# SmartVision.net
KiCad netlist of a schematic drawn in EAGLE
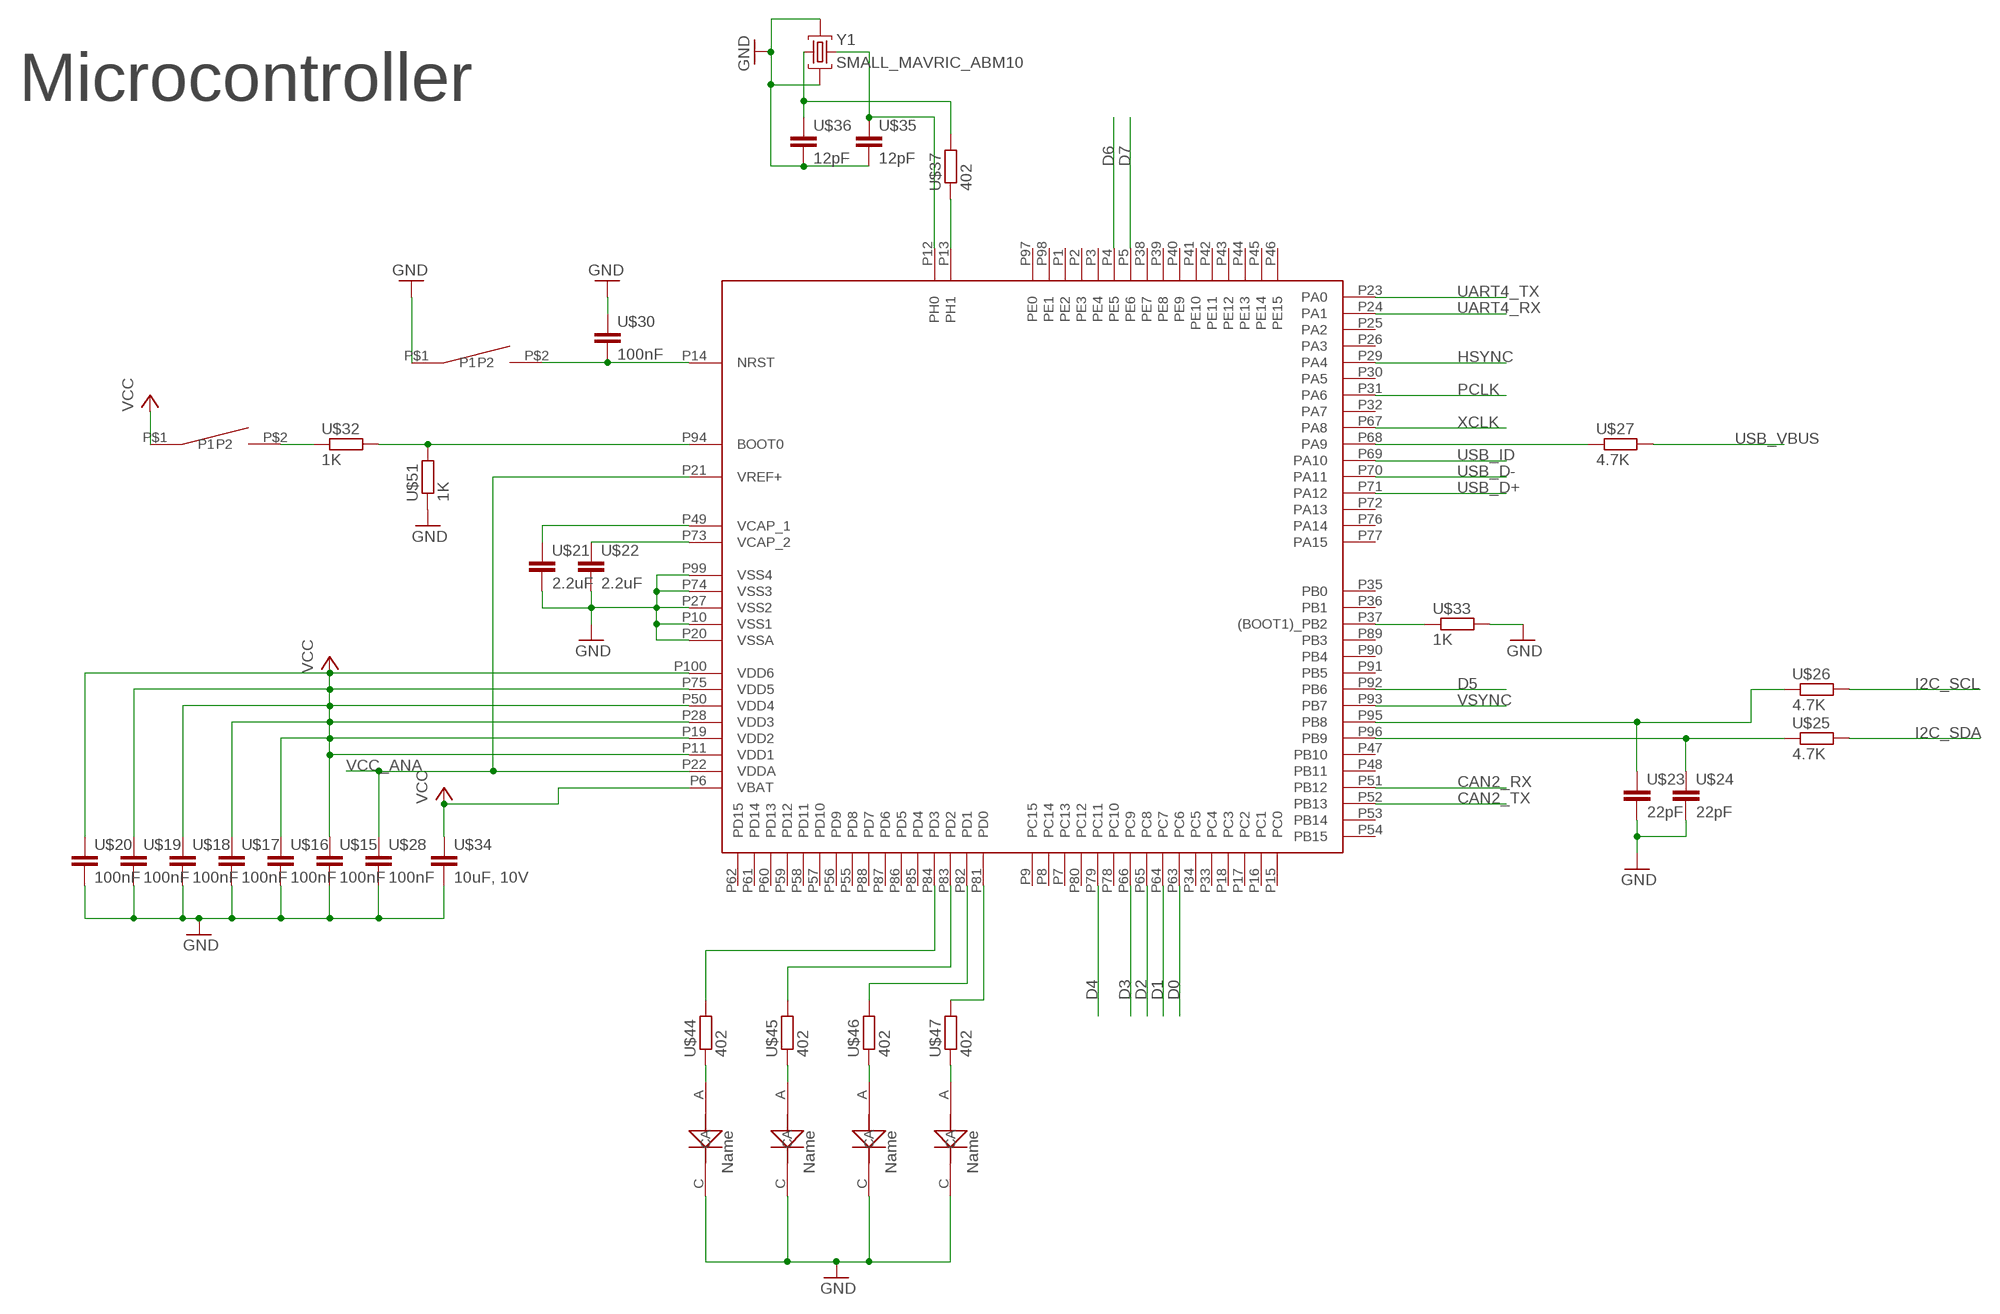
[diagram p0: schematic, sheet 1]
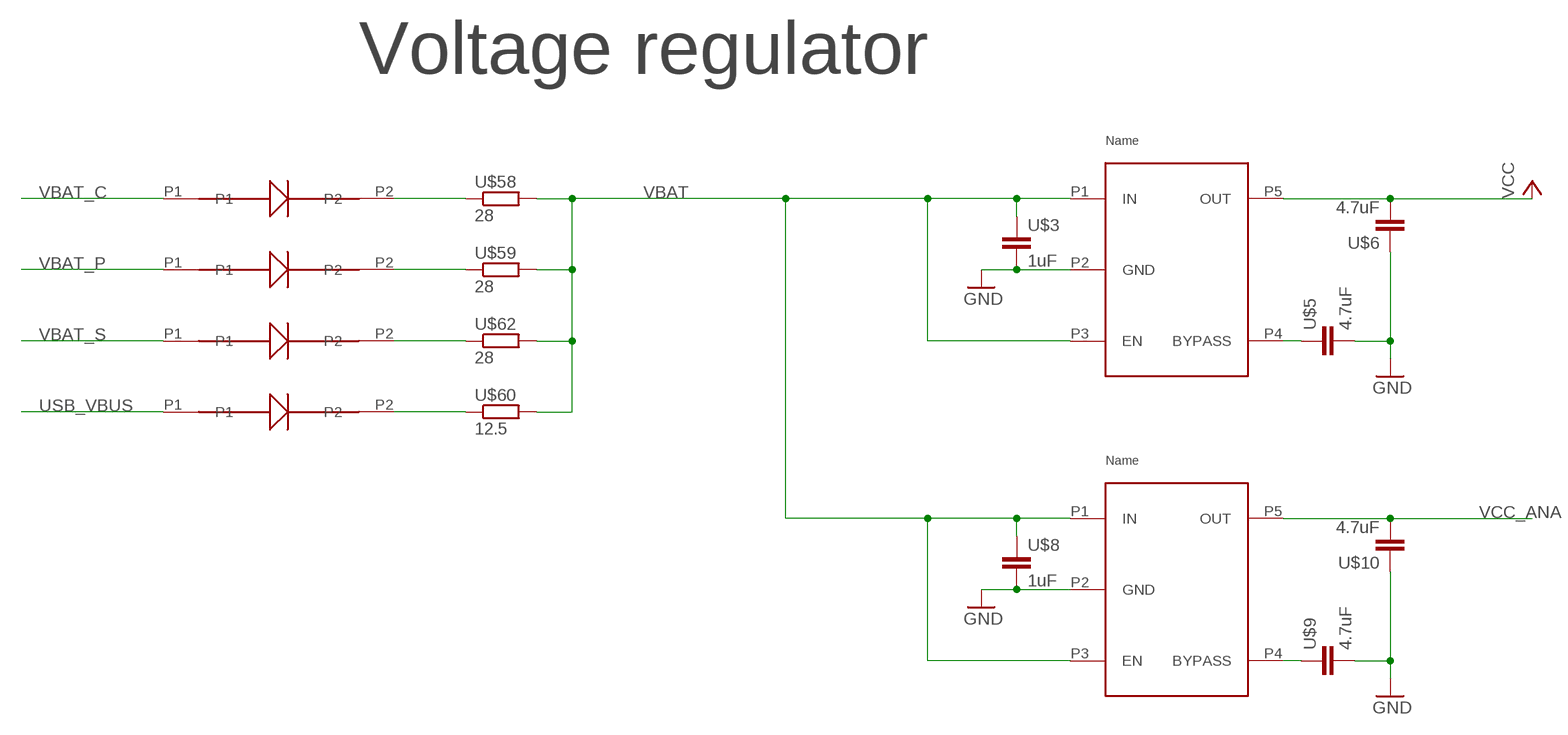
[diagram p1: schematic, sheet 2]
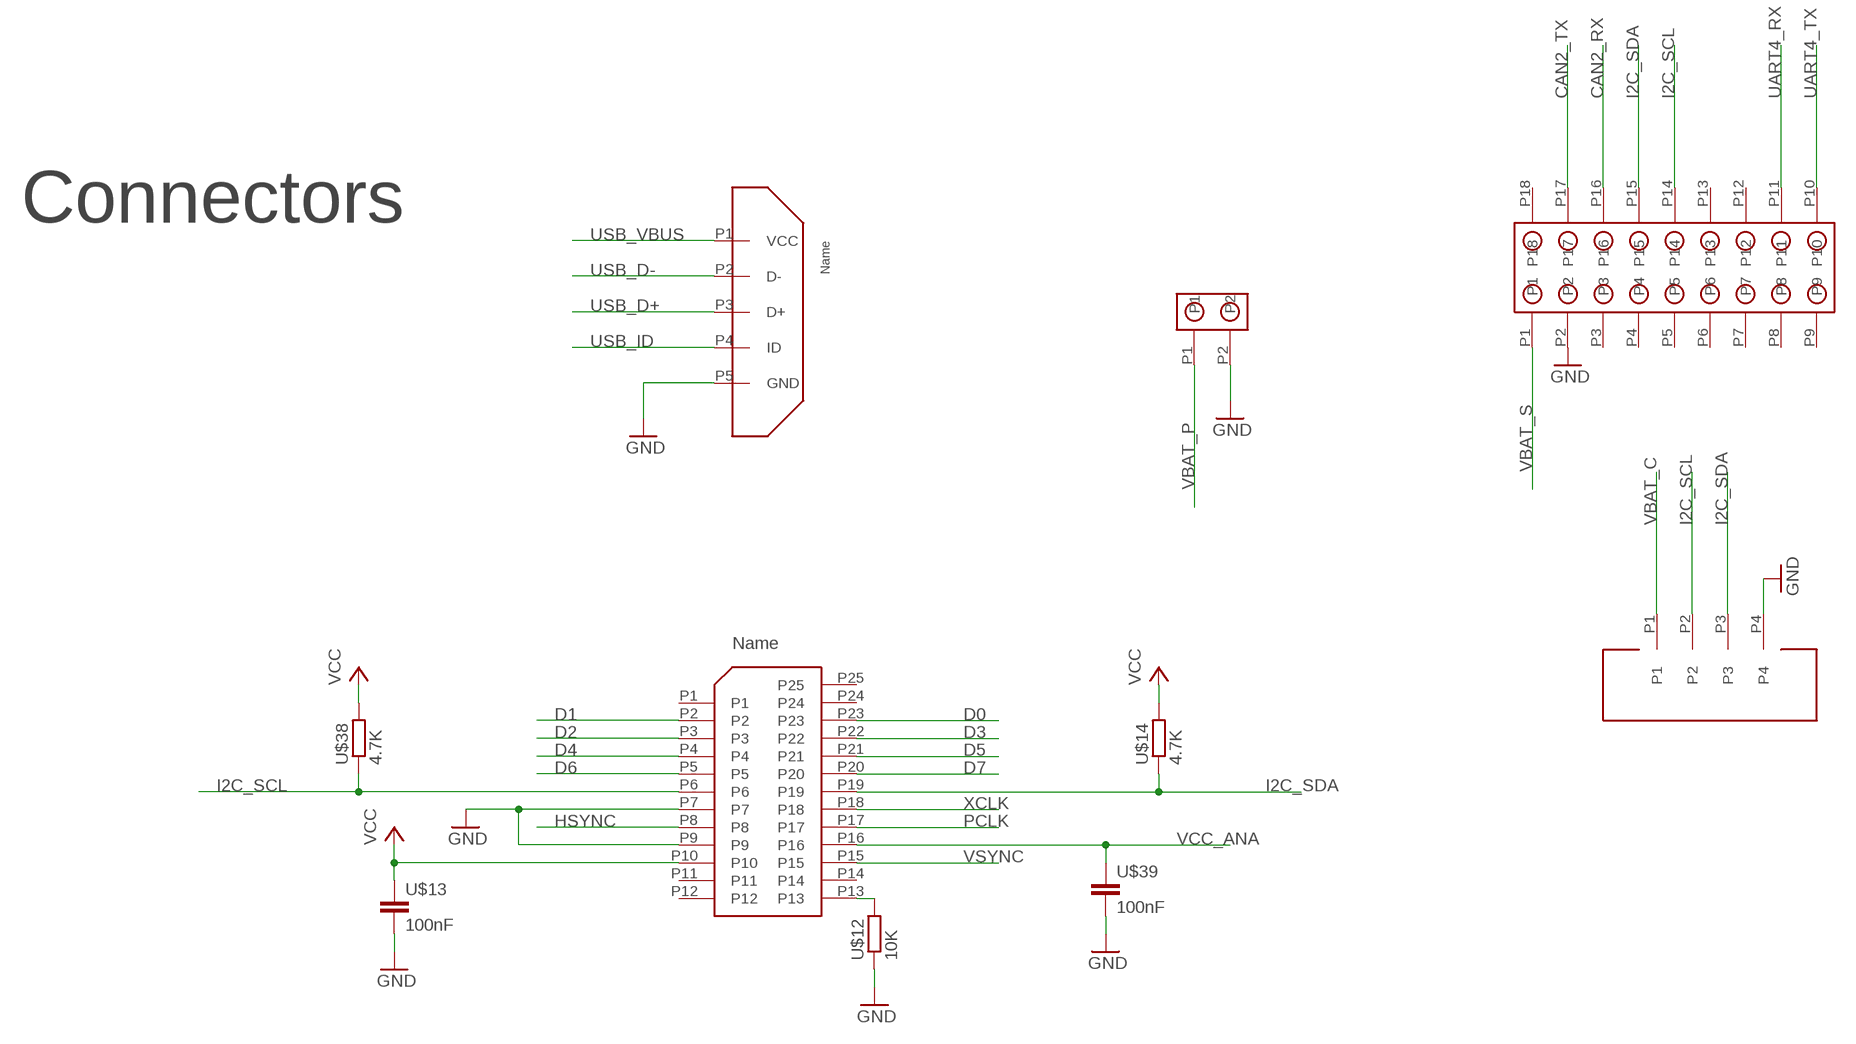
[diagram p2: schematic, sheet 3]
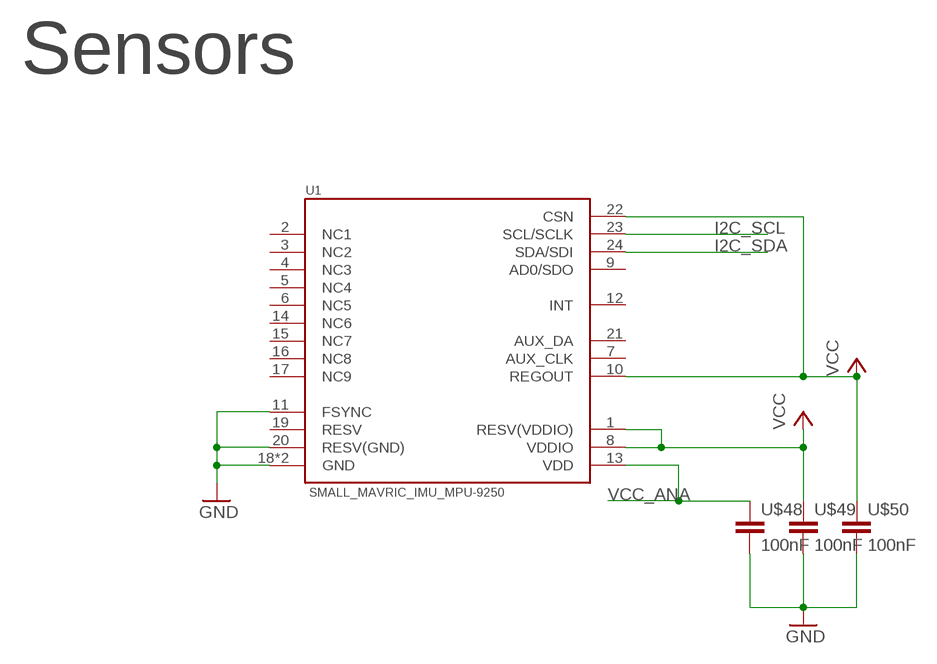
[diagram p3: schematic, sheet 4]

(export (version "E")
  (design (tool "Eeschema 10.0.6"))
  (components
    (comp (ref "U$1")
      (value "STM32F407VGT6-100")
      (footprint "eagle-import:STM32F407VGT6-100")
      (libsource (lib "eagle-import") (part "STM32F407VGT6-100"))
    )
    (comp (ref "U$15")
      (value "100nF")
      (footprint "eagle-import:SMALL_MAVRIC_SMALL_MAVRIC_CAPACITOR_C0402")
      (fields (field (name "PLACE_PART") "YES"))
      (libsource (lib "eagle-import") (part "SMALL_MAVRIC_CAPACITOR_C0402"))
    )
    (comp (ref "U$16")
      (value "100nF")
      (footprint "eagle-import:SMALL_MAVRIC_SMALL_MAVRIC_CAPACITOR_C0402")
      (fields (field (name "PLACE_PART") "YES"))
      (libsource (lib "eagle-import") (part "SMALL_MAVRIC_CAPACITOR_C0402"))
    )
    (comp (ref "U$17")
      (value "100nF")
      (footprint "eagle-import:SMALL_MAVRIC_SMALL_MAVRIC_CAPACITOR_C0402")
      (fields (field (name "PLACE_PART") "YES"))
      (libsource (lib "eagle-import") (part "SMALL_MAVRIC_CAPACITOR_C0402"))
    )
    (comp (ref "U$18")
      (value "100nF")
      (footprint "eagle-import:SMALL_MAVRIC_SMALL_MAVRIC_CAPACITOR_C0402")
      (fields (field (name "PLACE_PART") "YES"))
      (libsource (lib "eagle-import") (part "SMALL_MAVRIC_CAPACITOR_C0402"))
    )
    (comp (ref "U$19")
      (value "100nF")
      (footprint "eagle-import:SMALL_MAVRIC_SMALL_MAVRIC_CAPACITOR_C0402")
      (fields (field (name "PLACE_PART") "YES"))
      (libsource (lib "eagle-import") (part "SMALL_MAVRIC_CAPACITOR_C0402"))
    )
    (comp (ref "U$20")
      (value "100nF")
      (footprint "eagle-import:SMALL_MAVRIC_SMALL_MAVRIC_CAPACITOR_C0402")
      (fields (field (name "PLACE_PART") "YES"))
      (libsource (lib "eagle-import") (part "SMALL_MAVRIC_CAPACITOR_C0402"))
    )
    (comp (ref "U$21")
      (value "2.2uF")
      (footprint "eagle-import:SMALL_MAVRIC_SMALL_MAVRIC_CAPACITOR_C0402")
      (fields (field (name "PLACE_PART") "YES"))
      (libsource (lib "eagle-import") (part "SMALL_MAVRIC_CAPACITOR_C0402"))
    )
    (comp (ref "U$22")
      (value "2.2uF")
      (footprint "eagle-import:SMALL_MAVRIC_SMALL_MAVRIC_CAPACITOR_C0402")
      (fields (field (name "PLACE_PART") "YES"))
      (libsource (lib "eagle-import") (part "SMALL_MAVRIC_CAPACITOR_C0402"))
    )
    (comp (ref "U$23")
      (value "22pF")
      (footprint "eagle-import:SMALL_MAVRIC_SMALL_MAVRIC_CAPACITOR_C0402")
      (fields (field (name "PLACE_PART") "YES"))
      (libsource (lib "eagle-import") (part "SMALL_MAVRIC_CAPACITOR_C0402"))
    )
    (comp (ref "U$24")
      (value "22pF")
      (footprint "eagle-import:SMALL_MAVRIC_SMALL_MAVRIC_CAPACITOR_C0402")
      (fields (field (name "PLACE_PART") "YES"))
      (libsource (lib "eagle-import") (part "SMALL_MAVRIC_CAPACITOR_C0402"))
    )
    (comp (ref "U$25")
      (value "4.7K")
      (footprint "eagle-import:SMALL_MAVRIC_SMALL_MAVRIC_RESISTOR_R0402")
      (fields (field (name "PLACE_PART") "YES"))
      (libsource (lib "eagle-import") (part "SMALL_MAVRIC_RESISTOR_R0402"))
    )
    (comp (ref "U$26")
      (value "4.7K")
      (footprint "eagle-import:SMALL_MAVRIC_SMALL_MAVRIC_RESISTOR_R0402")
      (fields (field (name "PLACE_PART") "YES"))
      (libsource (lib "eagle-import") (part "SMALL_MAVRIC_RESISTOR_R0402"))
    )
    (comp (ref "U$27")
      (value "4.7K")
      (footprint "eagle-import:SMALL_MAVRIC_SMALL_MAVRIC_RESISTOR_R0402")
      (fields (field (name "PLACE_PART") "YES"))
      (libsource (lib "eagle-import") (part "SMALL_MAVRIC_RESISTOR_R0402"))
    )
    (comp (ref "U$28")
      (value "100nF")
      (footprint "eagle-import:SMALL_MAVRIC_SMALL_MAVRIC_CAPACITOR_C0402")
      (fields (field (name "PLACE_PART") "YES"))
      (libsource (lib "eagle-import") (part "SMALL_MAVRIC_CAPACITOR_C0402"))
    )
    (comp (ref "U$29")
      (value "SWITCH_OFF_(ON)")
      (footprint "eagle-import:SWITCH_OFF_(ON)")
      (libsource (lib "eagle-import") (part "SWITCH_OFF_(ON)"))
    )
    (comp (ref "U$30")
      (value "100nF")
      (footprint "eagle-import:SMALL_MAVRIC_SMALL_MAVRIC_CAPACITOR_C0402")
      (fields (field (name "PLACE_PART") "YES"))
      (libsource (lib "eagle-import") (part "SMALL_MAVRIC_CAPACITOR_C0402"))
    )
    (comp (ref "U$31")
      (value "SWITCH_OFF_(ON)")
      (footprint "eagle-import:SWITCH_OFF_(ON)")
      (libsource (lib "eagle-import") (part "SWITCH_OFF_(ON)"))
    )
    (comp (ref "U$32")
      (value "1K")
      (footprint "eagle-import:SMALL_MAVRIC_SMALL_MAVRIC_RESISTOR_R0402")
      (fields (field (name "PLACE_PART") "YES"))
      (libsource (lib "eagle-import") (part "SMALL_MAVRIC_RESISTOR_R0402"))
    )
    (comp (ref "U$33")
      (value "1K")
      (footprint "eagle-import:SMALL_MAVRIC_SMALL_MAVRIC_RESISTOR_R0402")
      (fields (field (name "PLACE_PART") "YES"))
      (libsource (lib "eagle-import") (part "SMALL_MAVRIC_RESISTOR_R0402"))
    )
    (comp (ref "U$34")
      (value "10uF, 10V")
      (footprint "eagle-import:SMALL_MAVRIC_SMALL_MAVRIC_CAPACITOR_C0603")
      (fields (field (name "PLACE_PART") "YES"))
      (libsource (lib "eagle-import") (part "SMALL_MAVRIC_CAPACITOR_C0603"))
    )
    (comp (ref "U$35")
      (value "12pF")
      (footprint "eagle-import:SMALL_MAVRIC_SMALL_MAVRIC_CAPACITOR_C0402")
      (fields (field (name "PLACE_PART") "YES"))
      (libsource (lib "eagle-import") (part "SMALL_MAVRIC_CAPACITOR_C0402"))
    )
    (comp (ref "U$36")
      (value "12pF")
      (footprint "eagle-import:SMALL_MAVRIC_SMALL_MAVRIC_CAPACITOR_C0402")
      (fields (field (name "PLACE_PART") "YES"))
      (libsource (lib "eagle-import") (part "SMALL_MAVRIC_CAPACITOR_C0402"))
    )
    (comp (ref "U$37")
      (value "402")
      (footprint "eagle-import:SMALL_MAVRIC_SMALL_MAVRIC_RESISTOR_R0402")
      (fields (field (name "PLACE_PART") "YES"))
      (libsource (lib "eagle-import") (part "SMALL_MAVRIC_RESISTOR_R0402"))
    )
    (comp (ref "U$40")
      (value "LED")
      (footprint "eagle-import:LED")
      (libsource (lib "eagle-import") (part "LED"))
    )
    (comp (ref "U$41")
      (value "LED")
      (footprint "eagle-import:LED")
      (libsource (lib "eagle-import") (part "LED"))
    )
    (comp (ref "U$42")
      (value "LED")
      (footprint "eagle-import:LED")
      (libsource (lib "eagle-import") (part "LED"))
    )
    (comp (ref "U$43")
      (value "LED")
      (footprint "eagle-import:LED")
      (libsource (lib "eagle-import") (part "LED"))
    )
    (comp (ref "U$44")
      (value "402")
      (footprint "eagle-import:SMALL_MAVRIC_SMALL_MAVRIC_RESISTOR_R0402")
      (fields (field (name "PLACE_PART") "YES"))
      (libsource (lib "eagle-import") (part "SMALL_MAVRIC_RESISTOR_R0402"))
    )
    (comp (ref "U$45")
      (value "402")
      (footprint "eagle-import:SMALL_MAVRIC_SMALL_MAVRIC_RESISTOR_R0402")
      (fields (field (name "PLACE_PART") "YES"))
      (libsource (lib "eagle-import") (part "SMALL_MAVRIC_RESISTOR_R0402"))
    )
    (comp (ref "U$46")
      (value "402")
      (footprint "eagle-import:SMALL_MAVRIC_SMALL_MAVRIC_RESISTOR_R0402")
      (fields (field (name "PLACE_PART") "YES"))
      (libsource (lib "eagle-import") (part "SMALL_MAVRIC_RESISTOR_R0402"))
    )
    (comp (ref "U$47")
      (value "402")
      (footprint "eagle-import:SMALL_MAVRIC_SMALL_MAVRIC_RESISTOR_R0402")
      (fields (field (name "PLACE_PART") "YES"))
      (libsource (lib "eagle-import") (part "SMALL_MAVRIC_RESISTOR_R0402"))
    )
    (comp (ref "U$51")
      (value "1K")
      (footprint "eagle-import:SMALL_MAVRIC_SMALL_MAVRIC_RESISTOR_R0402")
      (fields (field (name "PLACE_PART") "YES"))
      (libsource (lib "eagle-import") (part "SMALL_MAVRIC_RESISTOR_R0402"))
    )
    (comp (ref "Y1")
      (value "SMALL_MAVRIC_ABM10")
      (footprint "eagle-import:SMALL_MAVRIC_OSCILLATOR_ABM10")
      (libsource (lib "eagle-import") (part "SMALL_MAVRIC_ABM10"))
    )
    (comp (ref "U$48")
      (value "100nF")
      (footprint "eagle-import:SMALL_MAVRIC_SMALL_MAVRIC_CAPACITOR_C0402")
      (fields (field (name "PLACE_PART") "YES"))
      (libsource (lib "eagle-import") (part "SMALL_MAVRIC_CAPACITOR_C0402"))
    )
    (comp (ref "U$49")
      (value "100nF")
      (footprint "eagle-import:SMALL_MAVRIC_SMALL_MAVRIC_CAPACITOR_C0402")
      (fields (field (name "PLACE_PART") "YES"))
      (libsource (lib "eagle-import") (part "SMALL_MAVRIC_CAPACITOR_C0402"))
    )
    (comp (ref "U$50")
      (value "100nF")
      (footprint "eagle-import:SMALL_MAVRIC_SMALL_MAVRIC_CAPACITOR_C0402")
      (fields (field (name "PLACE_PART") "YES"))
      (libsource (lib "eagle-import") (part "SMALL_MAVRIC_CAPACITOR_C0402"))
    )
    (comp (ref "U1")
      (value "SMALL_MAVRIC_IMU_MPU-9250")
      (footprint "eagle-import:SMALL_MAVRIC_SMALL_MAVRIC_QFN-24_3.0X3.0MM")
      (fields (field (name "PLACE_PART") "YES"))
      (libsource (lib "eagle-import") (part "SMALL_MAVRIC_IMU_MPU-9250"))
    )
    (comp (ref "U$2")
      (value "VOLTAGE_REGULATOR_3V")
      (footprint "eagle-import:VOLTAGE_REGULATOR_3V")
      (libsource (lib "eagle-import") (part "VOLTAGE_REGULATOR_3V"))
    )
    (comp (ref "U$3")
      (value "1uF")
      (footprint "eagle-import:SMALL_MAVRIC_SMALL_MAVRIC_CAPACITOR_C0402")
      (fields (field (name "PLACE_PART") "YES"))
      (libsource (lib "eagle-import") (part "SMALL_MAVRIC_CAPACITOR_C0402"))
    )
    (comp (ref "U$5")
      (value "4.7uF")
      (footprint "eagle-import:SMALL_MAVRIC_SMALL_MAVRIC_CAPACITOR_C0603")
      (fields (field (name "PLACE_PART") "YES"))
      (libsource (lib "eagle-import") (part "SMALL_MAVRIC_CAPACITOR_C0603"))
    )
    (comp (ref "U$6")
      (value "4.7uF")
      (footprint "eagle-import:SMALL_MAVRIC_SMALL_MAVRIC_CAPACITOR_C0603")
      (fields (field (name "PLACE_PART") "YES"))
      (libsource (lib "eagle-import") (part "SMALL_MAVRIC_CAPACITOR_C0603"))
    )
    (comp (ref "U$7")
      (value "VOLTAGE_REGULATOR_3V")
      (footprint "eagle-import:VOLTAGE_REGULATOR_3V")
      (libsource (lib "eagle-import") (part "VOLTAGE_REGULATOR_3V"))
    )
    (comp (ref "U$8")
      (value "1uF")
      (footprint "eagle-import:SMALL_MAVRIC_SMALL_MAVRIC_CAPACITOR_C0402")
      (fields (field (name "PLACE_PART") "YES"))
      (libsource (lib "eagle-import") (part "SMALL_MAVRIC_CAPACITOR_C0402"))
    )
    (comp (ref "U$9")
      (value "4.7uF")
      (footprint "eagle-import:SMALL_MAVRIC_SMALL_MAVRIC_CAPACITOR_C0603")
      (fields (field (name "PLACE_PART") "YES"))
      (libsource (lib "eagle-import") (part "SMALL_MAVRIC_CAPACITOR_C0603"))
    )
    (comp (ref "U$10")
      (value "4.7uF")
      (footprint "eagle-import:SMALL_MAVRIC_SMALL_MAVRIC_CAPACITOR_C0603")
      (fields (field (name "PLACE_PART") "YES"))
      (libsource (lib "eagle-import") (part "SMALL_MAVRIC_CAPACITOR_C0603"))
    )
    (comp (ref "U$55")
      (value "DIODE_SCHOTTKY")
      (footprint "eagle-import:DIODE_SCHOTTKY")
      (libsource (lib "eagle-import") (part "DIODE_SCHOTTKY"))
    )
    (comp (ref "U$56")
      (value "DIODE_SCHOTTKY")
      (footprint "eagle-import:DIODE_SCHOTTKY")
      (libsource (lib "eagle-import") (part "DIODE_SCHOTTKY"))
    )
    (comp (ref "U$57")
      (value "DIODE_SCHOTTKY")
      (footprint "eagle-import:DIODE_SCHOTTKY")
      (libsource (lib "eagle-import") (part "DIODE_SCHOTTKY"))
    )
    (comp (ref "U$58")
      (value "28")
      (footprint "eagle-import:SMALL_MAVRIC_SMALL_MAVRIC_RESISTOR_R0402")
      (fields (field (name "PLACE_PART") "YES"))
      (libsource (lib "eagle-import") (part "SMALL_MAVRIC_RESISTOR_R0402"))
    )
    (comp (ref "U$59")
      (value "28")
      (footprint "eagle-import:SMALL_MAVRIC_SMALL_MAVRIC_RESISTOR_R0402")
      (fields (field (name "PLACE_PART") "YES"))
      (libsource (lib "eagle-import") (part "SMALL_MAVRIC_RESISTOR_R0402"))
    )
    (comp (ref "U$60")
      (value "12.5")
      (footprint "eagle-import:SMALL_MAVRIC_SMALL_MAVRIC_RESISTOR_R0402")
      (fields (field (name "PLACE_PART") "YES"))
      (libsource (lib "eagle-import") (part "SMALL_MAVRIC_RESISTOR_R0402"))
    )
    (comp (ref "U$61")
      (value "DIODE_SCHOTTKY")
      (footprint "eagle-import:DIODE_SCHOTTKY")
      (libsource (lib "eagle-import") (part "DIODE_SCHOTTKY"))
    )
    (comp (ref "U$62")
      (value "28")
      (footprint "eagle-import:SMALL_MAVRIC_SMALL_MAVRIC_RESISTOR_R0402")
      (fields (field (name "PLACE_PART") "YES"))
      (libsource (lib "eagle-import") (part "SMALL_MAVRIC_RESISTOR_R0402"))
    )
    (comp (ref "U$4")
      (value "MICRO_USB_PLUG")
      (footprint "eagle-import:MICRO_USB_PLUG")
      (libsource (lib "eagle-import") (part "MICRO_USB_PLUG"))
    )
    (comp (ref "U$11")
      (value "CON_CAMERA_FPC_25P_0.3MM")
      (footprint "eagle-import:CON_CAMERA_FPC_25P_0.3MM")
      (libsource (lib "eagle-import") (part "CON_CAMERA_FPC_25P_0.3MM"))
    )
    (comp (ref "U$12")
      (value "10K")
      (footprint "eagle-import:SMALL_MAVRIC_SMALL_MAVRIC_RESISTOR_R0402")
      (fields (field (name "PLACE_PART") "YES"))
      (libsource (lib "eagle-import") (part "SMALL_MAVRIC_RESISTOR_R0402"))
    )
    (comp (ref "U$13")
      (value "100nF")
      (footprint "eagle-import:SMALL_MAVRIC_SMALL_MAVRIC_CAPACITOR_C0402")
      (fields (field (name "PLACE_PART") "YES"))
      (libsource (lib "eagle-import") (part "SMALL_MAVRIC_CAPACITOR_C0402"))
    )
    (comp (ref "U$14")
      (value "4.7K")
      (footprint "eagle-import:SMALL_MAVRIC_SMALL_MAVRIC_RESISTOR_R0402")
      (fields (field (name "PLACE_PART") "YES"))
      (libsource (lib "eagle-import") (part "SMALL_MAVRIC_RESISTOR_R0402"))
    )
    (comp (ref "U$38")
      (value "4.7K")
      (footprint "eagle-import:SMALL_MAVRIC_SMALL_MAVRIC_RESISTOR_R0402")
      (fields (field (name "PLACE_PART") "YES"))
      (libsource (lib "eagle-import") (part "SMALL_MAVRIC_RESISTOR_R0402"))
    )
    (comp (ref "U$39")
      (value "100nF")
      (footprint "eagle-import:SMALL_MAVRIC_SMALL_MAVRIC_CAPACITOR_C0402")
      (fields (field (name "PLACE_PART") "YES"))
      (libsource (lib "eagle-import") (part "SMALL_MAVRIC_CAPACITOR_C0402"))
    )
    (comp (ref "U$52")
      (value "CON_2.54MM_18PINS_STACKABLE")
      (footprint "eagle-import:CON_2.54MM_18PINS_STACKABLE")
      (libsource (lib "eagle-import") (part "CON_2.54MM_18PINS_STACKABLE"))
    )
    (comp (ref "U$53")
      (value "CON_1.25MM_4PINS")
      (footprint "eagle-import:CON_1.25MM_4PINS")
      (libsource (lib "eagle-import") (part "CON_1.25MM_4PINS"))
    )
    (comp (ref "U$54")
      (value "CON_2.54MM_2PINS_STACKABLE")
      (footprint "eagle-import:CON_2.54MM_2PINS_STACKABLE")
      (libsource (lib "eagle-import") (part "CON_2.54MM_2PINS_STACKABLE"))
    )
  )
  (nets
    (net (code "1") (name "CAN2_RX") (class "Default")
      (node (ref "U$1") (pin "P51") (pinfunction "PB12_P51") (pintype "bidirectional"))
      (node (ref "U$52") (pin "P16") (pinfunction "P16_P16") (pintype "bidirectional"))
    )
    (net (code "2") (name "CAN2_TX") (class "Default")
      (node (ref "U$1") (pin "P52") (pinfunction "PB13_P52") (pintype "bidirectional"))
      (node (ref "U$52") (pin "P17") (pinfunction "P17_P17") (pintype "bidirectional"))
    )
    (net (code "3") (name "D0") (class "Default")
      (node (ref "U$1") (pin "P63") (pinfunction "PC6_P63") (pintype "bidirectional"))
      (node (ref "U$11") (pin "P23") (pinfunction "P23_P23") (pintype "bidirectional"))
    )
    (net (code "4") (name "D1") (class "Default")
      (node (ref "U$1") (pin "P64") (pinfunction "PC7_P64") (pintype "bidirectional"))
      (node (ref "U$11") (pin "P2") (pinfunction "P2_P2") (pintype "bidirectional"))
    )
    (net (code "5") (name "D2") (class "Default")
      (node (ref "U$1") (pin "P65") (pinfunction "PC8_P65") (pintype "bidirectional"))
      (node (ref "U$11") (pin "P3") (pinfunction "P3_P3") (pintype "bidirectional"))
    )
    (net (code "6") (name "D3") (class "Default")
      (node (ref "U$1") (pin "P66") (pinfunction "PC9_P66") (pintype "bidirectional"))
      (node (ref "U$11") (pin "P22") (pinfunction "P22_P22") (pintype "bidirectional"))
    )
    (net (code "7") (name "D4") (class "Default")
      (node (ref "U$1") (pin "P79") (pinfunction "PC11_P79") (pintype "bidirectional"))
      (node (ref "U$11") (pin "P4") (pinfunction "P4_P4") (pintype "bidirectional"))
    )
    (net (code "8") (name "D5") (class "Default")
      (node (ref "U$1") (pin "P92") (pinfunction "PB6_P92") (pintype "bidirectional"))
      (node (ref "U$11") (pin "P21") (pinfunction "P21_P21") (pintype "bidirectional"))
    )
    (net (code "9") (name "D6") (class "Default")
      (node (ref "U$1") (pin "P4") (pinfunction "PE5_P4") (pintype "bidirectional"))
      (node (ref "U$11") (pin "P5") (pinfunction "P5_P5") (pintype "bidirectional"))
    )
    (net (code "10") (name "D7") (class "Default")
      (node (ref "U$1") (pin "P5") (pinfunction "PE6_P5") (pintype "bidirectional"))
      (node (ref "U$11") (pin "P20") (pinfunction "P20_P20") (pintype "bidirectional"))
    )
    (net (code "11") (name "GND") (class "Default")
      (node (ref "U$1") (pin "P10") (pinfunction "VSS1_P10") (pintype "bidirectional"))
      (node (ref "U$1") (pin "P20") (pinfunction "VSSA_P20") (pintype "bidirectional"))
      (node (ref "U$1") (pin "P27") (pinfunction "VSS2_P27") (pintype "bidirectional"))
      (node (ref "U$1") (pin "P74") (pinfunction "VSS3_P74") (pintype "bidirectional"))
      (node (ref "U$1") (pin "P99") (pinfunction "VSS4_P99") (pintype "bidirectional"))
      (node (ref "U$10") (pin "1") (pinfunction "1_1") (pintype "passive"))
      (node (ref "U$11") (pin "P7") (pinfunction "P7_P7") (pintype "bidirectional"))
      (node (ref "U$11") (pin "P9") (pinfunction "P9_P9") (pintype "bidirectional"))
      (node (ref "U$12") (pin "1") (pinfunction "1_1") (pintype "passive"))
      (node (ref "U$13") (pin "2") (pinfunction "2_2") (pintype "passive"))
      (node (ref "U$15") (pin "2") (pinfunction "2_2") (pintype "passive"))
      (node (ref "U$16") (pin "2") (pinfunction "2_2") (pintype "passive"))
      (node (ref "U$17") (pin "2") (pinfunction "2_2") (pintype "passive"))
      (node (ref "U$18") (pin "2") (pinfunction "2_2") (pintype "passive"))
      (node (ref "U$19") (pin "2") (pinfunction "2_2") (pintype "passive"))
      (node (ref "U$2") (pin "P2") (pinfunction "GND_P2") (pintype "bidirectional"))
      (node (ref "U$20") (pin "2") (pinfunction "2_2") (pintype "passive"))
      (node (ref "U$21") (pin "2") (pinfunction "2_2") (pintype "passive"))
      (node (ref "U$22") (pin "2") (pinfunction "2_2") (pintype "passive"))
      (node (ref "U$23") (pin "2") (pinfunction "2_2") (pintype "passive"))
      (node (ref "U$24") (pin "2") (pinfunction "2_2") (pintype "passive"))
      (node (ref "U$28") (pin "2") (pinfunction "2_2") (pintype "passive"))
      (node (ref "U$29") (pin "P$1") (pinfunction "P1_P$1") (pintype "bidirectional"))
      (node (ref "U$3") (pin "2") (pinfunction "2_2") (pintype "passive"))
      (node (ref "U$30") (pin "1") (pinfunction "1_1") (pintype "passive"))
      (node (ref "U$33") (pin "2") (pinfunction "2_2") (pintype "passive"))
      (node (ref "U$34") (pin "2") (pinfunction "2_2") (pintype "passive"))
      (node (ref "U$35") (pin "2") (pinfunction "2_2") (pintype "passive"))
      (node (ref "U$36") (pin "2") (pinfunction "2_2") (pintype "passive"))
      (node (ref "U$39") (pin "2") (pinfunction "2_2") (pintype "passive"))
      (node (ref "U$4") (pin "P5") (pinfunction "GND_P5") (pintype "bidirectional"))
      (node (ref "U$40") (pin "C") (pinfunction "C_C") (pintype "bidirectional"))
      (node (ref "U$41") (pin "C") (pinfunction "C_C") (pintype "bidirectional"))
      (node (ref "U$42") (pin "C") (pinfunction "C_C") (pintype "bidirectional"))
      (node (ref "U$43") (pin "C") (pinfunction "C_C") (pintype "bidirectional"))
      (node (ref "U$48") (pin "2") (pinfunction "2_2") (pintype "passive"))
      (node (ref "U$49") (pin "2") (pinfunction "2_2") (pintype "passive"))
      (node (ref "U$5") (pin "2") (pinfunction "2_2") (pintype "passive"))
      (node (ref "U$50") (pin "2") (pinfunction "2_2") (pintype "passive"))
      (node (ref "U$51") (pin "1") (pinfunction "1_1") (pintype "passive"))
      (node (ref "U$52") (pin "P2") (pinfunction "P2_P2") (pintype "bidirectional"))
      (node (ref "U$53") (pin "P4") (pinfunction "P4_P4") (pintype "bidirectional"))
      (node (ref "U$54") (pin "P2") (pinfunction "P2_P2") (pintype "bidirectional"))
      (node (ref "U$6") (pin "1") (pinfunction "1_1") (pintype "passive"))
      (node (ref "U$7") (pin "P2") (pinfunction "GND_P2") (pintype "bidirectional"))
      (node (ref "U$8") (pin "2") (pinfunction "2_2") (pintype "passive"))
      (node (ref "U$9") (pin "2") (pinfunction "2_2") (pintype "passive"))
      (node (ref "U1") (pin "11") (pinfunction "FSYNC_11") (pintype "bidirectional"))
      (node (ref "U1") (pin "18") (pinfunction "GND_18") (pintype "power_in"))
      (node (ref "U1") (pin "20") (pinfunction "RESV(GND)_20") (pintype "passive"))
      (node (ref "U1") (pin "CENTRAL_PAD") (pinfunction "GND_CENTRAL_PAD") (pintype "power_in"))
      (node (ref "Y1") (pin "2") (pinfunction "2_2") (pintype "passive"))
      (node (ref "Y1") (pin "4") (pinfunction "4_4") (pintype "passive"))
    )
    (net (code "12") (name "HSYNC") (class "Default")
      (node (ref "U$1") (pin "P29") (pinfunction "PA4_P29") (pintype "bidirectional"))
      (node (ref "U$11") (pin "P8") (pinfunction "P8_P8") (pintype "bidirectional"))
    )
    (net (code "13") (name "I2C_SCL") (class "Default")
      (node (ref "U$11") (pin "P6") (pinfunction "P6_P6") (pintype "bidirectional"))
      (node (ref "U$26") (pin "2") (pinfunction "2_2") (pintype "passive"))
      (node (ref "U$38") (pin "1") (pinfunction "1_1") (pintype "passive"))
      (node (ref "U$52") (pin "P14") (pinfunction "P14_P14") (pintype "bidirectional"))
      (node (ref "U$53") (pin "P2") (pinfunction "P2_P2") (pintype "bidirectional"))
      (node (ref "U1") (pin "23") (pinfunction "SCL/SCLK_23") (pintype "input"))
    )
    (net (code "14") (name "I2C_SDA") (class "Default")
      (node (ref "U$11") (pin "P19") (pinfunction "P19_P19") (pintype "bidirectional"))
      (node (ref "U$14") (pin "1") (pinfunction "1_1") (pintype "passive"))
      (node (ref "U$25") (pin "2") (pinfunction "2_2") (pintype "passive"))
      (node (ref "U$52") (pin "P15") (pinfunction "P15_P15") (pintype "bidirectional"))
      (node (ref "U$53") (pin "P3") (pinfunction "P3_P3") (pintype "bidirectional"))
      (node (ref "U1") (pin "24") (pinfunction "SDA/SDI_24") (pintype "input"))
    )
    (net (code "15") (name "Net-(U$1-(BOOT1)_PB2)") (class "Default")
      (node (ref "U$1") (pin "P37") (pinfunction "(BOOT1)_PB2_P37") (pintype "bidirectional"))
      (node (ref "U$33") (pin "1") (pinfunction "1_1") (pintype "passive"))
    )
    (net (code "16") (name "Net-(U$1-BOOT0)") (class "Default")
      (node (ref "U$1") (pin "P94") (pinfunction "BOOT0_P94") (pintype "bidirectional"))
      (node (ref "U$32") (pin "2") (pinfunction "2_2") (pintype "passive"))
      (node (ref "U$51") (pin "2") (pinfunction "2_2") (pintype "passive"))
    )
    (net (code "17") (name "Net-(U$1-NRST)") (class "Default")
      (node (ref "U$1") (pin "P14") (pinfunction "NRST_P14") (pintype "bidirectional"))
      (node (ref "U$29") (pin "P$2") (pinfunction "P2_P$2") (pintype "bidirectional"))
      (node (ref "U$30") (pin "2") (pinfunction "2_2") (pintype "passive"))
    )
    (net (code "18") (name "Net-(U$1-PA9)") (class "Default")
      (node (ref "U$1") (pin "P68") (pinfunction "PA9_P68") (pintype "bidirectional"))
      (node (ref "U$27") (pin "1") (pinfunction "1_1") (pintype "passive"))
    )
    (net (code "19") (name "Net-(U$1-PB8)") (class "Default")
      (node (ref "U$1") (pin "P95") (pinfunction "PB8_P95") (pintype "bidirectional"))
      (node (ref "U$23") (pin "1") (pinfunction "1_1") (pintype "passive"))
      (node (ref "U$26") (pin "1") (pinfunction "1_1") (pintype "passive"))
    )
    (net (code "20") (name "Net-(U$1-PB9)") (class "Default")
      (node (ref "U$1") (pin "P96") (pinfunction "PB9_P96") (pintype "bidirectional"))
      (node (ref "U$24") (pin "1") (pinfunction "1_1") (pintype "passive"))
      (node (ref "U$25") (pin "1") (pinfunction "1_1") (pintype "passive"))
    )
    (net (code "21") (name "Net-(U$1-PD0)") (class "Default")
      (node (ref "U$1") (pin "P81") (pinfunction "PD0_P81") (pintype "bidirectional"))
      (node (ref "U$47") (pin "2") (pinfunction "2_2") (pintype "passive"))
    )
    (net (code "22") (name "Net-(U$1-PD1)") (class "Default")
      (node (ref "U$1") (pin "P82") (pinfunction "PD1_P82") (pintype "bidirectional"))
      (node (ref "U$46") (pin "2") (pinfunction "2_2") (pintype "passive"))
    )
    (net (code "23") (name "Net-(U$1-PD2)") (class "Default")
      (node (ref "U$1") (pin "P83") (pinfunction "PD2_P83") (pintype "bidirectional"))
      (node (ref "U$45") (pin "2") (pinfunction "2_2") (pintype "passive"))
    )
    (net (code "24") (name "Net-(U$1-PD3)") (class "Default")
      (node (ref "U$1") (pin "P84") (pinfunction "PD3_P84") (pintype "bidirectional"))
      (node (ref "U$44") (pin "2") (pinfunction "2_2") (pintype "passive"))
    )
    (net (code "25") (name "Net-(U$1-PH0)") (class "Default")
      (node (ref "U$1") (pin "P12") (pinfunction "PH0_P12") (pintype "bidirectional"))
      (node (ref "U$35") (pin "1") (pinfunction "1_1") (pintype "passive"))
      (node (ref "Y1") (pin "3") (pinfunction "3_3") (pintype "passive"))
    )
    (net (code "26") (name "Net-(U$1-PH1)") (class "Default")
      (node (ref "U$1") (pin "P13") (pinfunction "PH1_P13") (pintype "bidirectional"))
      (node (ref "U$37") (pin "1") (pinfunction "1_1") (pintype "passive"))
    )
    (net (code "27") (name "Net-(U$1-VCAP_1)") (class "Default")
      (node (ref "U$1") (pin "P49") (pinfunction "VCAP_1_P49") (pintype "bidirectional"))
      (node (ref "U$21") (pin "1") (pinfunction "1_1") (pintype "passive"))
    )
    (net (code "28") (name "Net-(U$1-VCAP_2)") (class "Default")
      (node (ref "U$1") (pin "P73") (pinfunction "VCAP_2_P73") (pintype "bidirectional"))
      (node (ref "U$22") (pin "1") (pinfunction "1_1") (pintype "passive"))
    )
    (net (code "29") (name "Net-(U$2-BYPASS)") (class "Default")
      (node (ref "U$2") (pin "P4") (pinfunction "BYPASS_P4") (pintype "bidirectional"))
      (node (ref "U$5") (pin "1") (pinfunction "1_1") (pintype "passive"))
    )
    (net (code "30") (name "Net-(U$7-BYPASS)") (class "Default")
      (node (ref "U$7") (pin "P4") (pinfunction "BYPASS_P4") (pintype "bidirectional"))
      (node (ref "U$9") (pin "1") (pinfunction "1_1") (pintype "passive"))
    )
    (net (code "31") (name "Net-(U$11-PadP13)") (class "Default")
      (node (ref "U$11") (pin "P13") (pinfunction "P13_P13") (pintype "bidirectional"))
      (node (ref "U$12") (pin "2") (pinfunction "2_2") (pintype "passive"))
    )
    (net (code "32") (name "Net-(U$31-P2)") (class "Default")
      (node (ref "U$31") (pin "P$2") (pinfunction "P2_P$2") (pintype "bidirectional"))
      (node (ref "U$32") (pin "1") (pinfunction "1_1") (pintype "passive"))
    )
    (net (code "33") (name "Net-(U$36-Pad1)") (class "Default")
      (node (ref "U$36") (pin "1") (pinfunction "1_1") (pintype "passive"))
      (node (ref "U$37") (pin "2") (pinfunction "2_2") (pintype "passive"))
      (node (ref "Y1") (pin "1") (pinfunction "1_1") (pintype "passive"))
    )
    (net (code "34") (name "Net-(U$40-PadA)") (class "Default")
      (node (ref "U$40") (pin "A") (pinfunction "A_A") (pintype "bidirectional"))
      (node (ref "U$44") (pin "1") (pinfunction "1_1") (pintype "passive"))
    )
    (net (code "35") (name "Net-(U$41-PadA)") (class "Default")
      (node (ref "U$41") (pin "A") (pinfunction "A_A") (pintype "bidirectional"))
      (node (ref "U$45") (pin "1") (pinfunction "1_1") (pintype "passive"))
    )
    (net (code "36") (name "Net-(U$42-PadA)") (class "Default")
      (node (ref "U$42") (pin "A") (pinfunction "A_A") (pintype "bidirectional"))
      (node (ref "U$46") (pin "1") (pinfunction "1_1") (pintype "passive"))
    )
    (net (code "37") (name "Net-(U$43-PadA)") (class "Default")
      (node (ref "U$43") (pin "A") (pinfunction "A_A") (pintype "bidirectional"))
      (node (ref "U$47") (pin "1") (pinfunction "1_1") (pintype "passive"))
    )
    (net (code "38") (name "Net-(U$55-PadP2)") (class "Default")
      (node (ref "U$55") (pin "P2") (pinfunction "P2_P2") (pintype "bidirectional"))
      (node (ref "U$58") (pin "1") (pinfunction "1_1") (pintype "passive"))
    )
    (net (code "39") (name "Net-(U$56-PadP2)") (class "Default")
      (node (ref "U$56") (pin "P2") (pinfunction "P2_P2") (pintype "bidirectional"))
      (node (ref "U$59") (pin "1") (pinfunction "1_1") (pintype "passive"))
    )
    (net (code "40") (name "Net-(U$57-PadP2)") (class "Default")
      (node (ref "U$57") (pin "P2") (pinfunction "P2_P2") (pintype "bidirectional"))
      (node (ref "U$60") (pin "1") (pinfunction "1_1") (pintype "passive"))
    )
    (net (code "41") (name "Net-(U$61-PadP2)") (class "Default")
      (node (ref "U$61") (pin "P2") (pinfunction "P2_P2") (pintype "bidirectional"))
      (node (ref "U$62") (pin "1") (pinfunction "1_1") (pintype "passive"))
    )
    (net (code "42") (name "PCLK") (class "Default")
      (node (ref "U$1") (pin "P31") (pinfunction "PA6_P31") (pintype "bidirectional"))
      (node (ref "U$11") (pin "P17") (pinfunction "P17_P17") (pintype "bidirectional"))
    )
    (net (code "43") (name "UART4_RX") (class "Default")
      (node (ref "U$1") (pin "P24") (pinfunction "PA1_P24") (pintype "bidirectional"))
      (node (ref "U$52") (pin "P11") (pinfunction "P11_P11") (pintype "bidirectional"))
    )
    (net (code "44") (name "UART4_TX") (class "Default")
      (node (ref "U$1") (pin "P23") (pinfunction "PA0_P23") (pintype "bidirectional"))
      (node (ref "U$52") (pin "P10") (pinfunction "P10_P10") (pintype "bidirectional"))
    )
    (net (code "45") (name "USB_D+") (class "Default")
      (node (ref "U$1") (pin "P71") (pinfunction "PA12_P71") (pintype "bidirectional"))
      (node (ref "U$4") (pin "P3") (pinfunction "D+_P3") (pintype "bidirectional"))
    )
    (net (code "46") (name "USB_D-") (class "Default")
      (node (ref "U$1") (pin "P70") (pinfunction "PA11_P70") (pintype "bidirectional"))
      (node (ref "U$4") (pin "P2") (pinfunction "D-_P2") (pintype "bidirectional"))
    )
    (net (code "47") (name "USB_ID") (class "Default")
      (node (ref "U$1") (pin "P69") (pinfunction "PA10_P69") (pintype "bidirectional"))
      (node (ref "U$4") (pin "P4") (pinfunction "ID_P4") (pintype "bidirectional"))
    )
    (net (code "48") (name "USB_VBUS") (class "Default")
      (node (ref "U$27") (pin "2") (pinfunction "2_2") (pintype "passive"))
      (node (ref "U$4") (pin "P1") (pinfunction "VCC_P1") (pintype "bidirectional"))
      (node (ref "U$57") (pin "P1") (pinfunction "P1_P1") (pintype "bidirectional"))
    )
    (net (code "49") (name "VBAT") (class "Default")
      (node (ref "U$2") (pin "P1") (pinfunction "IN_P1") (pintype "bidirectional"))
      (node (ref "U$2") (pin "P3") (pinfunction "EN_P3") (pintype "bidirectional"))
      (node (ref "U$3") (pin "1") (pinfunction "1_1") (pintype "passive"))
      (node (ref "U$58") (pin "2") (pinfunction "2_2") (pintype "passive"))
      (node (ref "U$59") (pin "2") (pinfunction "2_2") (pintype "passive"))
      (node (ref "U$60") (pin "2") (pinfunction "2_2") (pintype "passive"))
      (node (ref "U$62") (pin "2") (pinfunction "2_2") (pintype "passive"))
      (node (ref "U$7") (pin "P1") (pinfunction "IN_P1") (pintype "bidirectional"))
      (node (ref "U$7") (pin "P3") (pinfunction "EN_P3") (pintype "bidirectional"))
      (node (ref "U$8") (pin "1") (pinfunction "1_1") (pintype "passive"))
    )
    (net (code "50") (name "VBAT_C") (class "Default")
      (node (ref "U$53") (pin "P1") (pinfunction "P1_P1") (pintype "bidirectional"))
      (node (ref "U$55") (pin "P1") (pinfunction "P1_P1") (pintype "bidirectional"))
    )
    (net (code "51") (name "VBAT_P") (class "Default")
      (node (ref "U$54") (pin "P1") (pinfunction "P1_P1") (pintype "bidirectional"))
      (node (ref "U$56") (pin "P1") (pinfunction "P1_P1") (pintype "bidirectional"))
    )
    (net (code "52") (name "VBAT_S") (class "Default")
      (node (ref "U$52") (pin "P1") (pinfunction "P1_P1") (pintype "bidirectional"))
      (node (ref "U$61") (pin "P1") (pinfunction "P1_P1") (pintype "bidirectional"))
    )
    (net (code "53") (name "VCC") (class "Default")
      (node (ref "U$1") (pin "P100") (pinfunction "VDD6_P100") (pintype "bidirectional"))
      (node (ref "U$1") (pin "P11") (pinfunction "VDD1_P11") (pintype "bidirectional"))
      (node (ref "U$1") (pin "P19") (pinfunction "VDD2_P19") (pintype "bidirectional"))
      (node (ref "U$1") (pin "P28") (pinfunction "VDD3_P28") (pintype "bidirectional"))
      (node (ref "U$1") (pin "P50") (pinfunction "VDD4_P50") (pintype "bidirectional"))
      (node (ref "U$1") (pin "P6") (pinfunction "VBAT_P6") (pintype "bidirectional"))
      (node (ref "U$1") (pin "P75") (pinfunction "VDD5_P75") (pintype "bidirectional"))
      (node (ref "U$11") (pin "P10") (pinfunction "P10_P10") (pintype "bidirectional"))
      (node (ref "U$13") (pin "1") (pinfunction "1_1") (pintype "passive"))
      (node (ref "U$14") (pin "2") (pinfunction "2_2") (pintype "passive"))
      (node (ref "U$15") (pin "1") (pinfunction "1_1") (pintype "passive"))
      (node (ref "U$16") (pin "1") (pinfunction "1_1") (pintype "passive"))
      (node (ref "U$17") (pin "1") (pinfunction "1_1") (pintype "passive"))
      (node (ref "U$18") (pin "1") (pinfunction "1_1") (pintype "passive"))
      (node (ref "U$19") (pin "1") (pinfunction "1_1") (pintype "passive"))
      (node (ref "U$2") (pin "P5") (pinfunction "OUT_P5") (pintype "bidirectional"))
      (node (ref "U$20") (pin "1") (pinfunction "1_1") (pintype "passive"))
      (node (ref "U$31") (pin "P$1") (pinfunction "P1_P$1") (pintype "bidirectional"))
      (node (ref "U$34") (pin "1") (pinfunction "1_1") (pintype "passive"))
      (node (ref "U$38") (pin "2") (pinfunction "2_2") (pintype "passive"))
      (node (ref "U$49") (pin "1") (pinfunction "1_1") (pintype "passive"))
      (node (ref "U$50") (pin "1") (pinfunction "1_1") (pintype "passive"))
      (node (ref "U$6") (pin "2") (pinfunction "2_2") (pintype "passive"))
      (node (ref "U1") (pin "1") (pinfunction "RESV(VDDIO)_1") (pintype "passive"))
      (node (ref "U1") (pin "10") (pinfunction "REGOUT_10") (pintype "passive"))
      (node (ref "U1") (pin "22") (pinfunction "CSN_22") (pintype "input"))
      (node (ref "U1") (pin "8") (pinfunction "VDDIO_8") (pintype "power_in"))
    )
    (net (code "54") (name "VCC_ANA") (class "Default")
      (node (ref "U$1") (pin "P21") (pinfunction "VREF+_P21") (pintype "bidirectional"))
      (node (ref "U$1") (pin "P22") (pinfunction "VDDA_P22") (pintype "bidirectional"))
      (node (ref "U$10") (pin "2") (pinfunction "2_2") (pintype "passive"))
      (node (ref "U$11") (pin "P16") (pinfunction "P16_P16") (pintype "bidirectional"))
      (node (ref "U$28") (pin "1") (pinfunction "1_1") (pintype "passive"))
      (node (ref "U$39") (pin "1") (pinfunction "1_1") (pintype "passive"))
      (node (ref "U$48") (pin "1") (pinfunction "1_1") (pintype "passive"))
      (node (ref "U$7") (pin "P5") (pinfunction "OUT_P5") (pintype "bidirectional"))
      (node (ref "U1") (pin "13") (pinfunction "VDD_13") (pintype "power_in"))
    )
    (net (code "55") (name "VSYNC") (class "Default")
      (node (ref "U$1") (pin "P93") (pinfunction "PB7_P93") (pintype "bidirectional"))
      (node (ref "U$11") (pin "P15") (pinfunction "P15_P15") (pintype "bidirectional"))
    )
    (net (code "56") (name "XCLK") (class "Default")
      (node (ref "U$1") (pin "P67") (pinfunction "PA8_P67") (pintype "bidirectional"))
      (node (ref "U$11") (pin "P18") (pinfunction "P18_P18") (pintype "bidirectional"))
    )
    (net (code "57") (name "unconnected-(U$1-PA2-PadP25)") (class "Default")
      (node (ref "U$1") (pin "P25") (pinfunction "PA2_P25") (pintype "bidirectional"))
    )
    (net (code "58") (name "unconnected-(U$1-PA3-PadP26)") (class "Default")
      (node (ref "U$1") (pin "P26") (pinfunction "PA3_P26") (pintype "bidirectional"))
    )
    (net (code "59") (name "unconnected-(U$1-PA5-PadP30)") (class "Default")
      (node (ref "U$1") (pin "P30") (pinfunction "PA5_P30") (pintype "bidirectional"))
    )
    (net (code "60") (name "unconnected-(U$1-PA7-PadP32)") (class "Default")
      (node (ref "U$1") (pin "P32") (pinfunction "PA7_P32") (pintype "bidirectional"))
    )
    (net (code "61") (name "unconnected-(U$1-PA13-PadP72)") (class "Default")
      (node (ref "U$1") (pin "P72") (pinfunction "PA13_P72") (pintype "bidirectional"))
    )
    (net (code "62") (name "unconnected-(U$1-PA14-PadP76)") (class "Default")
      (node (ref "U$1") (pin "P76") (pinfunction "PA14_P76") (pintype "bidirectional"))
    )
    (net (code "63") (name "unconnected-(U$1-PA15-PadP77)") (class "Default")
      (node (ref "U$1") (pin "P77") (pinfunction "PA15_P77") (pintype "bidirectional"))
    )
    (net (code "64") (name "unconnected-(U$1-PB0-PadP35)") (class "Default")
      (node (ref "U$1") (pin "P35") (pinfunction "PB0_P35") (pintype "bidirectional"))
    )
    (net (code "65") (name "unconnected-(U$1-PB1-PadP36)") (class "Default")
      (node (ref "U$1") (pin "P36") (pinfunction "PB1_P36") (pintype "bidirectional"))
    )
    (net (code "66") (name "unconnected-(U$1-PB3-PadP89)") (class "Default")
      (node (ref "U$1") (pin "P89") (pinfunction "PB3_P89") (pintype "bidirectional"))
    )
    (net (code "67") (name "unconnected-(U$1-PB4-PadP90)") (class "Default")
      (node (ref "U$1") (pin "P90") (pinfunction "PB4_P90") (pintype "bidirectional"))
    )
    (net (code "68") (name "unconnected-(U$1-PB5-PadP91)") (class "Default")
      (node (ref "U$1") (pin "P91") (pinfunction "PB5_P91") (pintype "bidirectional"))
    )
    (net (code "69") (name "unconnected-(U$1-PB10-PadP47)") (class "Default")
      (node (ref "U$1") (pin "P47") (pinfunction "PB10_P47") (pintype "bidirectional"))
    )
    (net (code "70") (name "unconnected-(U$1-PB11-PadP48)") (class "Default")
      (node (ref "U$1") (pin "P48") (pinfunction "PB11_P48") (pintype "bidirectional"))
    )
    (net (code "71") (name "unconnected-(U$1-PB14-PadP53)") (class "Default")
      (node (ref "U$1") (pin "P53") (pinfunction "PB14_P53") (pintype "bidirectional"))
    )
    (net (code "72") (name "unconnected-(U$1-PB15-PadP54)") (class "Default")
      (node (ref "U$1") (pin "P54") (pinfunction "PB15_P54") (pintype "bidirectional"))
    )
    (net (code "73") (name "unconnected-(U$1-PC0-PadP15)") (class "Default")
      (node (ref "U$1") (pin "P15") (pinfunction "PC0_P15") (pintype "bidirectional"))
    )
    (net (code "74") (name "unconnected-(U$1-PC1-PadP16)") (class "Default")
      (node (ref "U$1") (pin "P16") (pinfunction "PC1_P16") (pintype "bidirectional"))
    )
    (net (code "75") (name "unconnected-(U$1-PC2-PadP17)") (class "Default")
      (node (ref "U$1") (pin "P17") (pinfunction "PC2_P17") (pintype "bidirectional"))
    )
    (net (code "76") (name "unconnected-(U$1-PC3-PadP18)") (class "Default")
      (node (ref "U$1") (pin "P18") (pinfunction "PC3_P18") (pintype "bidirectional"))
    )
    (net (code "77") (name "unconnected-(U$1-PC4-PadP33)") (class "Default")
      (node (ref "U$1") (pin "P33") (pinfunction "PC4_P33") (pintype "bidirectional"))
    )
    (net (code "78") (name "unconnected-(U$1-PC5-PadP34)") (class "Default")
      (node (ref "U$1") (pin "P34") (pinfunction "PC5_P34") (pintype "bidirectional"))
    )
    (net (code "79") (name "unconnected-(U$1-PC10-PadP78)") (class "Default")
      (node (ref "U$1") (pin "P78") (pinfunction "PC10_P78") (pintype "bidirectional"))
    )
    (net (code "80") (name "unconnected-(U$1-PC12-PadP80)") (class "Default")
      (node (ref "U$1") (pin "P80") (pinfunction "PC12_P80") (pintype "bidirectional"))
    )
    (net (code "81") (name "unconnected-(U$1-PC13-PadP7)") (class "Default")
      (node (ref "U$1") (pin "P7") (pinfunction "PC13_P7") (pintype "bidirectional"))
    )
    (net (code "82") (name "unconnected-(U$1-PC14-PadP8)") (class "Default")
      (node (ref "U$1") (pin "P8") (pinfunction "PC14_P8") (pintype "bidirectional"))
    )
    (net (code "83") (name "unconnected-(U$1-PC15-PadP9)") (class "Default")
      (node (ref "U$1") (pin "P9") (pinfunction "PC15_P9") (pintype "bidirectional"))
    )
    (net (code "84") (name "unconnected-(U$1-PD4-PadP85)") (class "Default")
      (node (ref "U$1") (pin "P85") (pinfunction "PD4_P85") (pintype "bidirectional"))
    )
    (net (code "85") (name "unconnected-(U$1-PD5-PadP86)") (class "Default")
      (node (ref "U$1") (pin "P86") (pinfunction "PD5_P86") (pintype "bidirectional"))
    )
    (net (code "86") (name "unconnected-(U$1-PD6-PadP87)") (class "Default")
      (node (ref "U$1") (pin "P87") (pinfunction "PD6_P87") (pintype "bidirectional"))
    )
    (net (code "87") (name "unconnected-(U$1-PD7-PadP88)") (class "Default")
      (node (ref "U$1") (pin "P88") (pinfunction "PD7_P88") (pintype "bidirectional"))
    )
    (net (code "88") (name "unconnected-(U$1-PD8-PadP55)") (class "Default")
      (node (ref "U$1") (pin "P55") (pinfunction "PD8_P55") (pintype "bidirectional"))
    )
    (net (code "89") (name "unconnected-(U$1-PD9-PadP56)") (class "Default")
      (node (ref "U$1") (pin "P56") (pinfunction "PD9_P56") (pintype "bidirectional"))
    )
    (net (code "90") (name "unconnected-(U$1-PD10-PadP57)") (class "Default")
      (node (ref "U$1") (pin "P57") (pinfunction "PD10_P57") (pintype "bidirectional"))
    )
    (net (code "91") (name "unconnected-(U$1-PD11-PadP58)") (class "Default")
      (node (ref "U$1") (pin "P58") (pinfunction "PD11_P58") (pintype "bidirectional"))
    )
    (net (code "92") (name "unconnected-(U$1-PD12-PadP59)") (class "Default")
      (node (ref "U$1") (pin "P59") (pinfunction "PD12_P59") (pintype "bidirectional"))
    )
    (net (code "93") (name "unconnected-(U$1-PD13-PadP60)") (class "Default")
      (node (ref "U$1") (pin "P60") (pinfunction "PD13_P60") (pintype "bidirectional"))
    )
    (net (code "94") (name "unconnected-(U$1-PD14-PadP61)") (class "Default")
      (node (ref "U$1") (pin "P61") (pinfunction "PD14_P61") (pintype "bidirectional"))
    )
    (net (code "95") (name "unconnected-(U$1-PD15-PadP62)") (class "Default")
      (node (ref "U$1") (pin "P62") (pinfunction "PD15_P62") (pintype "bidirectional"))
    )
    (net (code "96") (name "unconnected-(U$1-PE0-PadP97)") (class "Default")
      (node (ref "U$1") (pin "P97") (pinfunction "PE0_P97") (pintype "bidirectional"))
    )
    (net (code "97") (name "unconnected-(U$1-PE1-PadP98)") (class "Default")
      (node (ref "U$1") (pin "P98") (pinfunction "PE1_P98") (pintype "bidirectional"))
    )
    (net (code "98") (name "unconnected-(U$1-PE2-PadP1)") (class "Default")
      (node (ref "U$1") (pin "P1") (pinfunction "PE2_P1") (pintype "bidirectional"))
    )
    (net (code "99") (name "unconnected-(U$1-PE3-PadP2)") (class "Default")
      (node (ref "U$1") (pin "P2") (pinfunction "PE3_P2") (pintype "bidirectional"))
    )
    (net (code "100") (name "unconnected-(U$1-PE4-PadP3)") (class "Default")
      (node (ref "U$1") (pin "P3") (pinfunction "PE4_P3") (pintype "bidirectional"))
    )
    (net (code "101") (name "unconnected-(U$1-PE7-PadP38)") (class "Default")
      (node (ref "U$1") (pin "P38") (pinfunction "PE7_P38") (pintype "bidirectional"))
    )
    (net (code "102") (name "unconnected-(U$1-PE8-PadP39)") (class "Default")
      (node (ref "U$1") (pin "P39") (pinfunction "PE8_P39") (pintype "bidirectional"))
    )
    (net (code "103") (name "unconnected-(U$1-PE9-PadP40)") (class "Default")
      (node (ref "U$1") (pin "P40") (pinfunction "PE9_P40") (pintype "bidirectional"))
    )
    (net (code "104") (name "unconnected-(U$1-PE10-PadP41)") (class "Default")
      (node (ref "U$1") (pin "P41") (pinfunction "PE10_P41") (pintype "bidirectional"))
    )
    (net (code "105") (name "unconnected-(U$1-PE11-PadP42)") (class "Default")
      (node (ref "U$1") (pin "P42") (pinfunction "PE11_P42") (pintype "bidirectional"))
    )
    (net (code "106") (name "unconnected-(U$1-PE12-PadP43)") (class "Default")
      (node (ref "U$1") (pin "P43") (pinfunction "PE12_P43") (pintype "bidirectional"))
    )
    (net (code "107") (name "unconnected-(U$1-PE13-PadP44)") (class "Default")
      (node (ref "U$1") (pin "P44") (pinfunction "PE13_P44") (pintype "bidirectional"))
    )
    (net (code "108") (name "unconnected-(U$1-PE14-PadP45)") (class "Default")
      (node (ref "U$1") (pin "P45") (pinfunction "PE14_P45") (pintype "bidirectional"))
    )
    (net (code "109") (name "unconnected-(U$1-PE15-PadP46)") (class "Default")
      (node (ref "U$1") (pin "P46") (pinfunction "PE15_P46") (pintype "bidirectional"))
    )
    (net (code "110") (name "unconnected-(U$11-PadP1)") (class "Default")
      (node (ref "U$11") (pin "P1") (pinfunction "P1_P1") (pintype "bidirectional"))
    )
    (net (code "111") (name "unconnected-(U$11-PadP11)") (class "Default")
      (node (ref "U$11") (pin "P11") (pinfunction "P11_P11") (pintype "bidirectional"))
    )
    (net (code "112") (name "unconnected-(U$11-PadP12)") (class "Default")
      (node (ref "U$11") (pin "P12") (pinfunction "P12_P12") (pintype "bidirectional"))
    )
    (net (code "113") (name "unconnected-(U$11-PadP14)") (class "Default")
      (node (ref "U$11") (pin "P14") (pinfunction "P14_P14") (pintype "bidirectional"))
    )
    (net (code "114") (name "unconnected-(U$11-PadP24)") (class "Default")
      (node (ref "U$11") (pin "P24") (pinfunction "P24_P24") (pintype "bidirectional"))
    )
    (net (code "115") (name "unconnected-(U$11-PadP25)") (class "Default")
      (node (ref "U$11") (pin "P25") (pinfunction "P25_P25") (pintype "bidirectional"))
    )
    (net (code "116") (name "unconnected-(U$52-PadP3)") (class "Default")
      (node (ref "U$52") (pin "P3") (pinfunction "P3_P3") (pintype "bidirectional"))
    )
    (net (code "117") (name "unconnected-(U$52-PadP4)") (class "Default")
      (node (ref "U$52") (pin "P4") (pinfunction "P4_P4") (pintype "bidirectional"))
    )
    (net (code "118") (name "unconnected-(U$52-PadP5)") (class "Default")
      (node (ref "U$52") (pin "P5") (pinfunction "P5_P5") (pintype "bidirectional"))
    )
    (net (code "119") (name "unconnected-(U$52-PadP6)") (class "Default")
      (node (ref "U$52") (pin "P6") (pinfunction "P6_P6") (pintype "bidirectional"))
    )
    (net (code "120") (name "unconnected-(U$52-PadP7)") (class "Default")
      (node (ref "U$52") (pin "P7") (pinfunction "P7_P7") (pintype "bidirectional"))
    )
    (net (code "121") (name "unconnected-(U$52-PadP8)") (class "Default")
      (node (ref "U$52") (pin "P8") (pinfunction "P8_P8") (pintype "bidirectional"))
    )
    (net (code "122") (name "unconnected-(U$52-PadP9)") (class "Default")
      (node (ref "U$52") (pin "P9") (pinfunction "P9_P9") (pintype "bidirectional"))
    )
    (net (code "123") (name "unconnected-(U$52-PadP12)") (class "Default")
      (node (ref "U$52") (pin "P12") (pinfunction "P12_P12") (pintype "bidirectional"))
    )
    (net (code "124") (name "unconnected-(U$52-PadP13)") (class "Default")
      (node (ref "U$52") (pin "P13") (pinfunction "P13_P13") (pintype "bidirectional"))
    )
    (net (code "125") (name "unconnected-(U$52-PadP18)") (class "Default")
      (node (ref "U$52") (pin "P18") (pinfunction "P18_P18") (pintype "bidirectional"))
    )
    (net (code "126") (name "unconnected-(U1-AD0{slash}SDO-Pad9)") (class "Default")
      (node (ref "U1") (pin "9") (pinfunction "AD0/SDO_9") (pintype "bidirectional"))
    )
    (net (code "127") (name "unconnected-(U1-AUX_CLK-Pad7)") (class "Default")
      (node (ref "U1") (pin "7") (pinfunction "AUX_CLK_7") (pintype "open_collector"))
    )
    (net (code "128") (name "unconnected-(U1-AUX_DA-Pad21)") (class "Default")
      (node (ref "U1") (pin "21") (pinfunction "AUX_DA_21") (pintype "open_collector"))
    )
    (net (code "129") (name "unconnected-(U1-INT-Pad12)") (class "Default")
      (node (ref "U1") (pin "12") (pinfunction "INT_12") (pintype "open_collector"))
    )
    (net (code "130") (name "unconnected-(U1-NC1-Pad2)") (class "Default")
      (node (ref "U1") (pin "2") (pinfunction "NC1_2") (pintype "passive"))
    )
    (net (code "131") (name "unconnected-(U1-NC2-Pad3)") (class "Default")
      (node (ref "U1") (pin "3") (pinfunction "NC2_3") (pintype "passive"))
    )
    (net (code "132") (name "unconnected-(U1-NC3-Pad4)") (class "Default")
      (node (ref "U1") (pin "4") (pinfunction "NC3_4") (pintype "passive"))
    )
    (net (code "133") (name "unconnected-(U1-NC4-Pad5)") (class "Default")
      (node (ref "U1") (pin "5") (pinfunction "NC4_5") (pintype "passive"))
    )
    (net (code "134") (name "unconnected-(U1-NC5-Pad6)") (class "Default")
      (node (ref "U1") (pin "6") (pinfunction "NC5_6") (pintype "passive"))
    )
    (net (code "135") (name "unconnected-(U1-NC6-Pad14)") (class "Default")
      (node (ref "U1") (pin "14") (pinfunction "NC6_14") (pintype "passive"))
    )
    (net (code "136") (name "unconnected-(U1-NC7-Pad15)") (class "Default")
      (node (ref "U1") (pin "15") (pinfunction "NC7_15") (pintype "passive"))
    )
    (net (code "137") (name "unconnected-(U1-NC8-Pad16)") (class "Default")
      (node (ref "U1") (pin "16") (pinfunction "NC8_16") (pintype "passive"))
    )
    (net (code "138") (name "unconnected-(U1-NC9-Pad17)") (class "Default")
      (node (ref "U1") (pin "17") (pinfunction "NC9_17") (pintype "passive"))
    )
    (net (code "139") (name "unconnected-(U1-RESV-Pad19)") (class "Default")
      (node (ref "U1") (pin "19") (pinfunction "RESV_19") (pintype "passive"))
    )
  )
)
